# power-input.net
KiCad netlist of a schematic drawn in Altium Designer
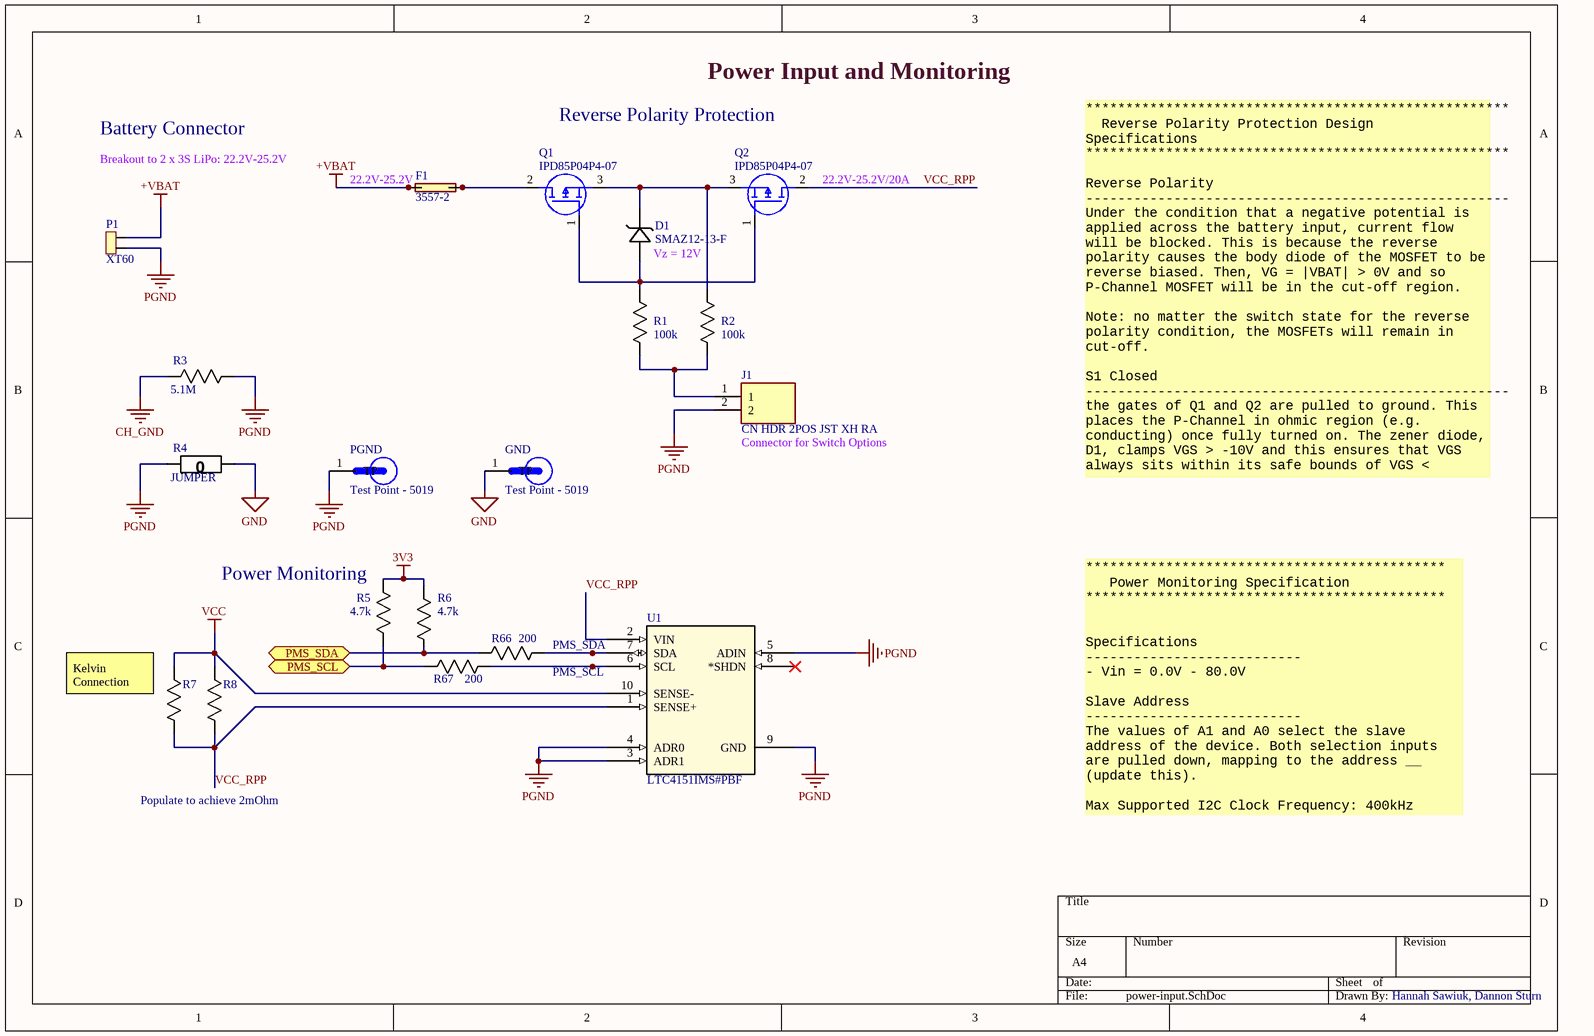
[diagram p0: power-input.SchDoc]

(export (version "E")
  (design (tool "Eeschema 10.0.6"))
  (components
    (comp (ref "D1")
      (value "SMAZ12-13-F")
      (footprint "SMA_DIO-L")
      (description "Zener Diode 12 V 1 W ±5% Surface Mount SMA")
      (fields
        (field (name "PART NUMBER") "DIODE ZENER 12V 1W")
        (field (name "COPYRIGHT") "Copyright (C) 2021 Ultra Librarian. All rights reserved.")
      )
      (libsource (lib "Diode_Library") (part "DIODE ZENER 12V 1W"))
    )
    (comp (ref "F1")
      (value "3557-2")
      (footprint "FUSE-3549-2")
      (description "Fuse Block 30A 500V 1 Circuit Blade Through Hole")
      (fields (field (name "MF") "Keystone Electronics") (field (name "PART NUMBER") "FUSE BLADE"))
      (libsource (lib "Fuse_Library") (part "FUSE BLADE"))
    )
    (comp (ref "GND")
      (value "Test Point - 5019")
      (footprint "TP380X203")
      (description "PC Test Point, Miniature Phosphor Bronze, Silver Plating Surface Mount Mounting Type")
      (fields (field (name "MP") "5019") (field (name "MF") "Keystone Electronics"))
      (libsource (lib "IC_Library") (part "Test Point - 5019"))
    )
    (comp (ref "J1")
      (value "CN HDR 2POS JST XH RA")
      (footprint "JST_S2B-XH-A(LF)(SN)")
      (description "Connector Header Through Hole 2 position right angle 0.098 _2.50mm_\r\nJST XH")
      (fields (field (name "MP") "B2B-XH-A_LF__SN_") (field (name "MF") "JST Sales"))
      (libsource (lib "Connector_Library") (part "CN HDR 2POS JST XH RA"))
    )
    (comp (ref "P1")
      (value "XT60")
      (footprint "Amass_XT60PW-M")
      (description "XT60 CONNECTORS FEMALE PAIR")
      (fields (field (name "MF") "SparkFun Electronics") (field (name "MP") "PRT-10474"))
      (libsource (lib "Connector_Library") (part "XT60 Connector"))
    )
    (comp (ref "PGND")
      (value "Test Point - 5019")
      (footprint "TP380X203")
      (description "PC Test Point, Miniature Phosphor Bronze, Silver Plating Surface Mount Mounting Type")
      (fields (field (name "MP") "5019") (field (name "MF") "Keystone Electronics"))
      (libsource (lib "IC_Library") (part "Test Point - 5019"))
    )
    (comp (ref "PMS_SCL")
      (value "Test Point (Via)")
      (footprint "TP")
      (libsource (lib "IC_Library") (part "Test Point (Via)"))
    )
    (comp (ref "PMS_SDA")
      (value "Test Point (Via)")
      (footprint "TP")
      (libsource (lib "IC_Library") (part "Test Point (Via)"))
    )
    (comp (ref "Q1")
      (value "IPD85P04P4-07")
      (footprint "DPAK (TO-252)")
      (description "P-Channel 40 V 85A (Tc) 88W (Tc) Surface Mount PG-TO252-3-313")
      (fields (field (name "PART NUMBER") "MOSFET IPD85P04P4-07"))
      (libsource (lib "Transistor_Library") (part "MOSFET IPD85P04P4-07"))
    )
    (comp (ref "Q2")
      (value "IPD85P04P4-07")
      (footprint "DPAK (TO-252)")
      (description "P-Channel 40 V 85A (Tc) 88W (Tc) Surface Mount PG-TO252-3-313")
      (fields (field (name "PART NUMBER") "MOSFET IPD85P04P4-07"))
      (libsource (lib "Transistor_Library") (part "MOSFET IPD85P04P4-07"))
    )
    (comp (ref "R1")
      (value "100k")
      (footprint "0603")
      (description "RES SMD 100K OHM 1% 1/8W 0603")
      (fields (field (name "TOLERANCE") "1%") (field (name "PART NUMBER") "RES 100k 1/8W - 1%"))
      (libsource (lib "Resistor_Library") (part "RES 100k 1/8W 1%"))
    )
    (comp (ref "R2")
      (value "100k")
      (footprint "0603")
      (description "RES SMD 100K OHM 1% 1/8W 0603")
      (fields (field (name "TOLERANCE") "1%") (field (name "PART NUMBER") "RES 100k 1/8W - 1%"))
      (libsource (lib "Resistor_Library") (part "RES 100k 1/8W 1%"))
    )
    (comp (ref "R3")
      (value "5.1M")
      (footprint "0603")
      (description "RES SMD 5.1 MOHM 5% 1/8W 0603")
      (fields (field (name "TOLERANCE") "5%") (field (name "PART NUMBER") "RES 5.1M 1/8W-5%"))
      (libsource (lib "Resistor_Library") (part "RES 5.1M 1/8W-5%"))
    )
    (comp (ref "R4")
      (value "JUMPER")
      (footprint "1210")
      (description "RES SMD 0 OHM JUMPER GENERIC 0603")
      (fields (field (name "PART NUMBER") "RES 0 JUMPER"))
      (libsource (lib "Resistor_Library") (part "RES 0 JUMPER"))
    )
    (comp (ref "R5")
      (value "4.7k")
      (footprint "0603")
      (description "RES SMD 4.7k OHM 5% 1/8W 0603")
      (fields (field (name "TOLERANCE") "5%") (field (name "PART NUMBER") "RES 4.7k 1/8W - 5%"))
      (libsource (lib "Resistor_Library") (part "RES 4.7k 1/8W - 5%"))
    )
    (comp (ref "R6")
      (value "4.7k")
      (footprint "0603")
      (description "RES SMD 4.7k OHM 5% 1/8W 0603")
      (fields (field (name "TOLERANCE") "5%") (field (name "PART NUMBER") "RES 4.7k 1/8W - 5%"))
      (libsource (lib "") (part "RES 4.7k 1/8W - 5%_1"))
    )
    (comp (ref "R7")
      (value "2mOHM")
      (footprint "2512")
      (description "RES SMD 2m OHM 1% 1W 2512")
      (fields (field (name "TOLERANCE") "1%") (field (name "PART NUMBER") "RES 2m 1W"))
      (libsource (lib "Resistor_Library") (part "RES 2m 1W"))
    )
    (comp (ref "R8")
      (value "2mOHM")
      (footprint "2512")
      (description "RES SMD 2m OHM 1% 1W 2512")
      (fields (field (name "TOLERANCE") "1%") (field (name "PART NUMBER") "RES 2m 1W"))
      (libsource (lib "Resistor_Library") (part "RES 2m 1W"))
    )
    (comp (ref "R66")
      (value "200")
      (footprint "0603")
      (description "RES SMD 200 OHM 5% 1/8W 0603")
      (fields (field (name "TOLERANCE") "5%") (field (name "PART NUMBER") "RES 200.0 1/8W"))
      (libsource (lib "Resistor_Library") (part "RES 200.0 1/8W"))
    )
    (comp (ref "R67")
      (value "200")
      (footprint "0603")
      (description "RES SMD 200 OHM 5% 1/8W 0603")
      (fields (field (name "TOLERANCE") "5%") (field (name "PART NUMBER") "RES 200.0 1/8W"))
      (libsource (lib "Resistor_Library") (part "RES 200.0 1/8W"))
    )
    (comp (ref "U1")
      (value "LTC4151IMS#PBF")
      (footprint "MSOP-10_MS_LIT")
      (description "IC CURRENT MONITOR(12BIT) 10MSOP")
      (fields
        (field (name "MANUFACTURER_PART_NUMBER") "ltc4151ims#pbf")
        (field (name "COPYRIGHT") "Copyright (C) 2021 Ultra Librarian. All rights reserved.")
      )
      (libsource (lib "IC_Library") (part "ltc4151ims#pbf"))
    )
  )
  (nets
    (net (code "1") (name "+VBAT") (class "Default")
      (node (ref "F1") (pin "3") (pinfunction "2A_3") (pintype "passive"))
      (node (ref "F1") (pin "4") (pinfunction "2B_4") (pintype "passive"))
      (node (ref "P1") (pin "2") (pinfunction "2_2") (pintype "passive"))
    )
    (net (code "2") (name "/PMS_SCL") (class "Default")
      (node (ref "R5") (pin "1") (pinfunction "R1_1") (pintype "passive"))
      (node (ref "R67") (pin "2") (pinfunction "R2_2") (pintype "passive"))
    )
    (net (code "3") (name "/PMS_SDA") (class "Default")
      (node (ref "R6") (pin "1") (pinfunction "R1_1") (pintype "passive"))
      (node (ref "R66") (pin "2") (pinfunction "R2_2") (pintype "passive"))
    )
    (net (code "4") (name "/VCC_RPP") (class "Default")
      (node (ref "Q2") (pin "2") (pinfunction "D_2") (pintype "passive"))
      (node (ref "R7") (pin "2") (pinfunction "R2_2") (pintype "passive"))
      (node (ref "R8") (pin "2") (pinfunction "R2_2") (pintype "passive"))
      (node (ref "U1") (pin "1") (pinfunction "SENSE+_1") (pintype "input"))
      (node (ref "U1") (pin "2") (pinfunction "VIN_2") (pintype "input"))
    )
    (net (code "5") (name "3V3") (class "Default")
      (node (ref "R5") (pin "2") (pinfunction "R2_2") (pintype "passive"))
      (node (ref "R6") (pin "2") (pinfunction "R2_2") (pintype "passive"))
    )
    (net (code "6") (name "CH_GND") (class "Default")
      (node (ref "R3") (pin "2") (pinfunction "R2_2") (pintype "passive"))
    )
    (net (code "7") (name "GND") (class "Default")
      (node (ref "GND") (pin "1") (pinfunction "TP_1") (pintype "passive"))
      (node (ref "R4") (pin "1") (pinfunction "R1_1") (pintype "passive"))
    )
    (net (code "8") (name "Net-(F1-1A)") (class "Default")
      (node (ref "F1") (pin "1") (pinfunction "1A_1") (pintype "passive"))
      (node (ref "F1") (pin "2") (pinfunction "1B_2") (pintype "passive"))
      (node (ref "Q1") (pin "2") (pinfunction "D_2") (pintype "passive"))
    )
    (net (code "9") (name "Net-(Q1-G)") (class "Default")
      (node (ref "D1") (pin "2") (pinfunction "2_2") (pintype "passive"))
      (node (ref "Q1") (pin "1") (pinfunction "G_1") (pintype "passive"))
      (node (ref "Q2") (pin "1") (pinfunction "G_1") (pintype "passive"))
      (node (ref "R1") (pin "1") (pinfunction "R1_1") (pintype "passive"))
    )
    (net (code "10") (name "Net-(Q1-S)") (class "Default")
      (node (ref "D1") (pin "1") (pinfunction "1_1") (pintype "passive"))
      (node (ref "Q1") (pin "3") (pinfunction "S_3") (pintype "passive"))
      (node (ref "Q2") (pin "3") (pinfunction "S_3") (pintype "passive"))
      (node (ref "R2") (pin "1") (pinfunction "R1_1") (pintype "passive"))
    )
    (net (code "11") (name "Net-(R1-R2)") (class "Default")
      (node (ref "J1") (pin "1") (pinfunction "1_1") (pintype "passive"))
      (node (ref "R1") (pin "2") (pinfunction "R2_2") (pintype "passive"))
      (node (ref "R2") (pin "2") (pinfunction "R2_2") (pintype "passive"))
    )
    (net (code "12") (name "Net-(R66-R1)") (class "Default")
      (node (ref "PMS_SDA") (pin "1") (pinfunction "1_1") (pintype "passive"))
      (node (ref "R66") (pin "1") (pinfunction "R1_1") (pintype "passive"))
      (node (ref "U1") (pin "7") (pinfunction "SDA_7") (pintype "bidirectional"))
    )
    (net (code "13") (name "Net-(R67-R1)") (class "Default")
      (node (ref "PMS_SCL") (pin "1") (pinfunction "1_1") (pintype "passive"))
      (node (ref "R67") (pin "1") (pinfunction "R1_1") (pintype "passive"))
      (node (ref "U1") (pin "6") (pinfunction "SCL_6") (pintype "input"))
    )
    (net (code "14") (name "PGND") (class "Default")
      (node (ref "J1") (pin "2") (pinfunction "2_2") (pintype "passive"))
      (node (ref "P1") (pin "1") (pinfunction "1_1") (pintype "passive"))
      (node (ref "PGND") (pin "1") (pinfunction "TP_1") (pintype "passive"))
      (node (ref "R3") (pin "1") (pinfunction "R1_1") (pintype "passive"))
      (node (ref "R4") (pin "2") (pinfunction "R2_2") (pintype "passive"))
      (node (ref "U1") (pin "3") (pinfunction "ADR1_3") (pintype "input"))
      (node (ref "U1") (pin "4") (pinfunction "ADR0_4") (pintype "input"))
      (node (ref "U1") (pin "5") (pinfunction "ADIN_5") (pintype "input"))
      (node (ref "U1") (pin "9") (pinfunction "GND_9") (pintype "power_in"))
    )
    (net (code "15") (name "VCC") (class "Default")
      (node (ref "R7") (pin "1") (pinfunction "R1_1") (pintype "passive"))
      (node (ref "R8") (pin "1") (pinfunction "R1_1") (pintype "passive"))
      (node (ref "U1") (pin "10") (pinfunction "SENSE-_10") (pintype "input"))
    )
    (net (code "16") (name "unconnected-(U1-*SHDN-Pad8)") (class "Default")
      (node (ref "U1") (pin "8") (pinfunction "*SHDN_8") (pintype "input+no_connect"))
    )
  )
)
